# uc4h_esc_mini_v100.net
KiCad netlist of a schematic drawn in EAGLE
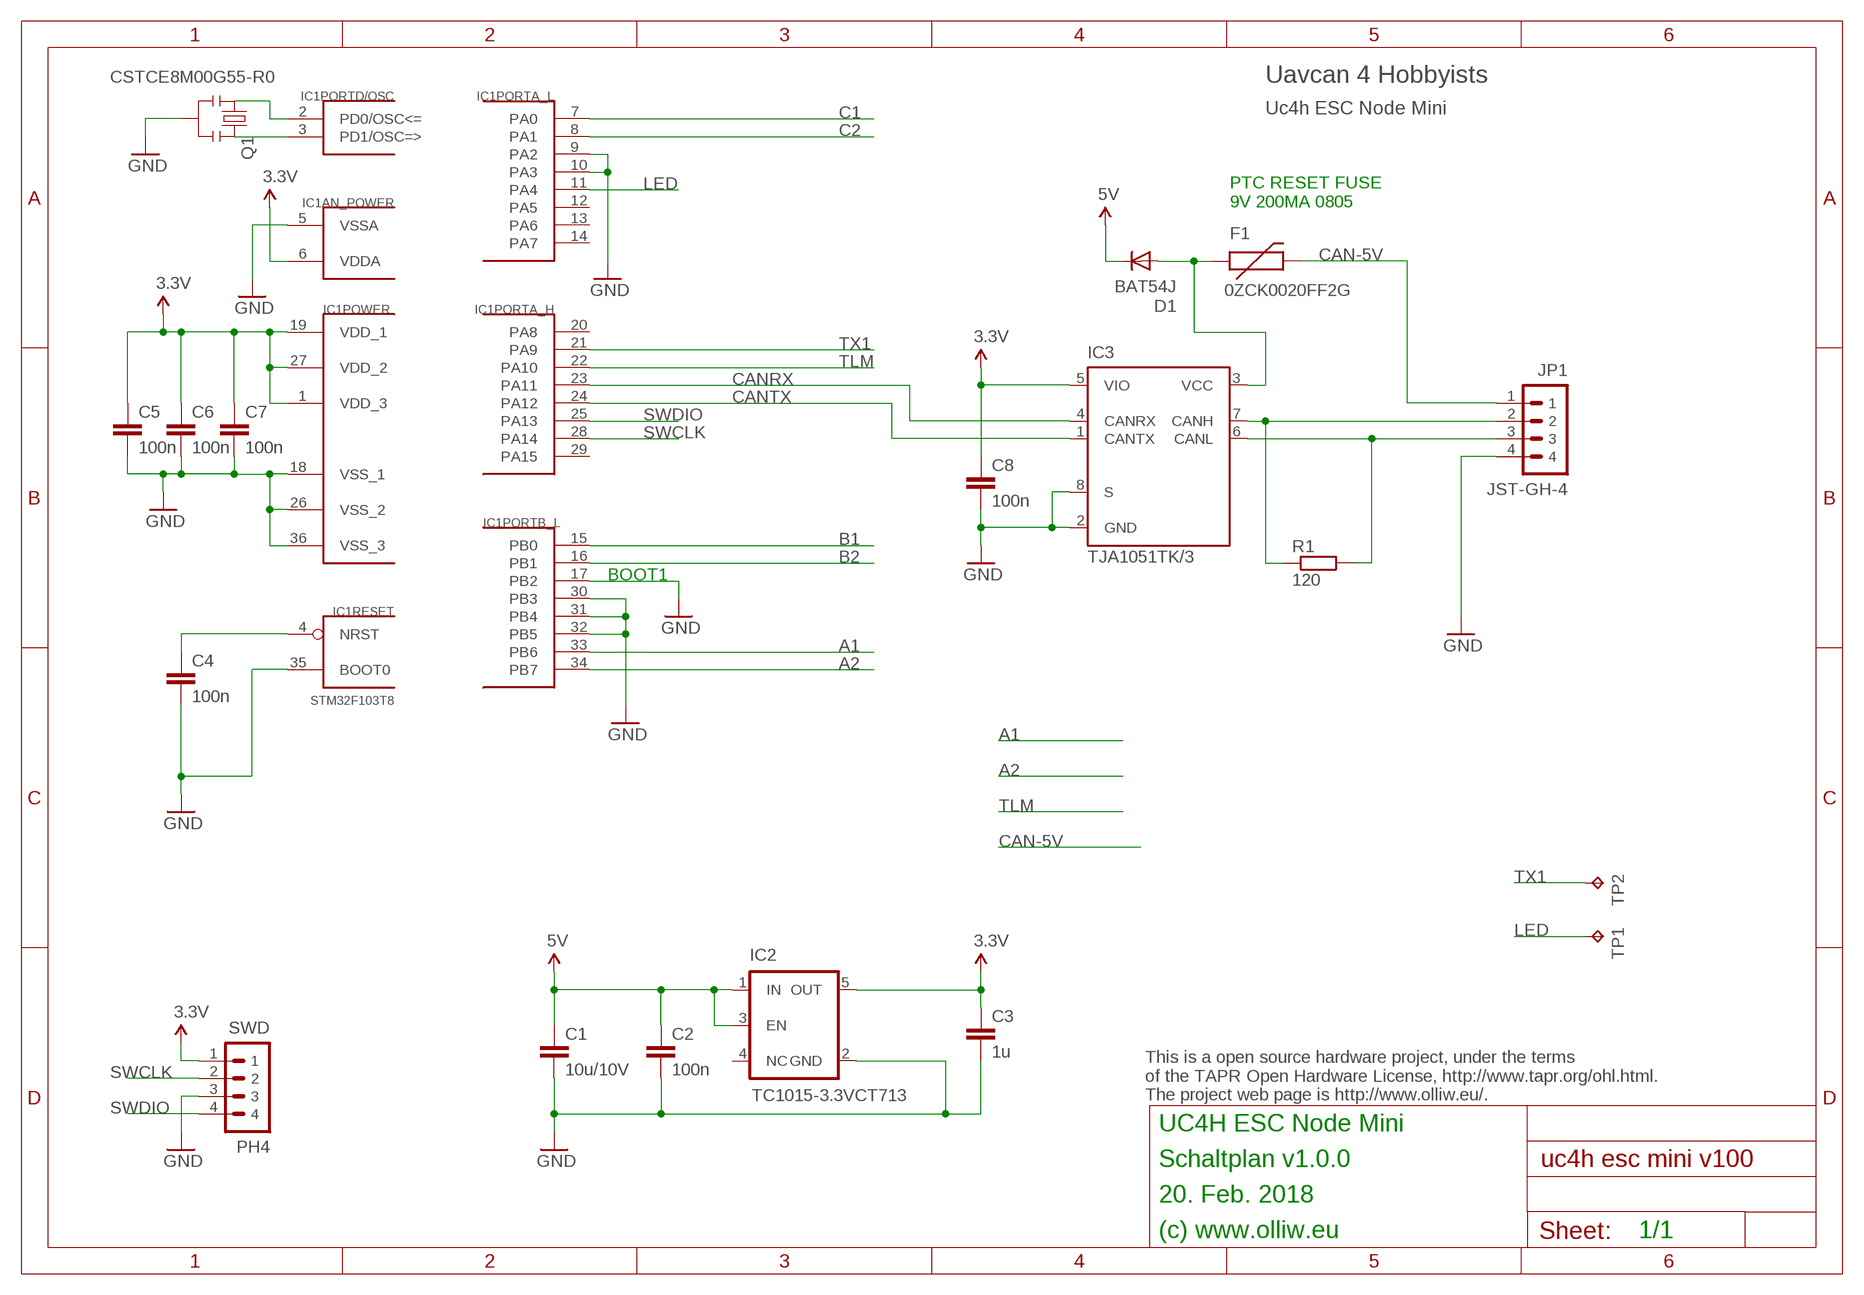
[diagram p0: schematic, sheet 1]

(export (version "E")
  (design (tool "Eeschema 10.0.6"))
  (components
    (comp (ref "C1")
      (value "10u/10V")
      (footprint "eagle-import:C1206")
      (libsource (lib "eagle-import") (part "C-EUC1206"))
    )
    (comp (ref "C2")
      (value "100n")
      (footprint "eagle-import:C0603K")
      (libsource (lib "eagle-import") (part "C-EUC0603K"))
    )
    (comp (ref "C3")
      (value "1u")
      (footprint "eagle-import:C0603K")
      (libsource (lib "eagle-import") (part "C-EUC0603K"))
    )
    (comp (ref "C4")
      (value "100n")
      (footprint "eagle-import:C0603K")
      (libsource (lib "eagle-import") (part "C-EUC0603K"))
    )
    (comp (ref "C5")
      (value "100n")
      (footprint "eagle-import:C0603K")
      (libsource (lib "eagle-import") (part "C-EUC0603K"))
    )
    (comp (ref "C6")
      (value "100n")
      (footprint "eagle-import:C0603K")
      (libsource (lib "eagle-import") (part "C-EUC0603K"))
    )
    (comp (ref "C7")
      (value "100n")
      (footprint "eagle-import:C0603K")
      (libsource (lib "eagle-import") (part "C-EUC0603K"))
    )
    (comp (ref "C8")
      (value "100n")
      (footprint "eagle-import:C0603K")
      (libsource (lib "eagle-import") (part "C-EUC0603K"))
    )
    (comp (ref "D1")
      (value "BAT54J")
      (footprint "eagle-import:SOD110-R")
      (libsource (lib "eagle-import") (part "DIODE-SOD110-R"))
    )
    (comp (ref "F1")
      (value "0ZCK0020FF2G")
      (footprint "eagle-import:FUSE-0805")
      (libsource (lib "eagle-import") (part "FUSE-PTCFUSE-0805"))
    )
    (comp (ref "IC1")
      (value "STM32F103T8")
      (footprint "eagle-import:VFQFPN36")
      (libsource (lib "eagle-import") (part "STM32F10XTXU6"))
    )
    (comp (ref "IC2")
      (value "TC1015-3.3VCT713")
      (footprint "eagle-import:SOT23-5")
      (libsource (lib "eagle-import") (part "V_REG_TPS76433SOT23-5"))
    )
    (comp (ref "IC3")
      (value "TJA1051TK/3")
      (footprint "eagle-import:HVSON8")
      (libsource (lib "eagle-import") (part "TJA1051TK/3"))
    )
    (comp (ref "JP1")
      (value "JST-GH-4")
      (footprint "eagle-import:SM04B-GHS-TB")
      (libsource (lib "eagle-import") (part "JST-GH-4"))
    )
    (comp (ref "Q1")
      (value "CSTCE8M00G55-R0")
      (footprint "eagle-import:RESONATOR-SMD")
      (libsource (lib "eagle-import") (part "RESONATORSMD"))
    )
    (comp (ref "R1")
      (value "120")
      (footprint "eagle-import:R0603")
      (libsource (lib "eagle-import") (part "R-EU_R0603"))
    )
    (comp (ref "SWD")
      (value "PH4")
      (footprint "eagle-import:4X1_1P27_OCT_BILEX")
      (libsource (lib "eagle-import") (part "P4X1_1P27-OCT_BILEX"))
    )
    (comp (ref "TP1")
      (value "TPB1,27")
      (footprint "eagle-import:B1,27")
      (libsource (lib "eagle-import") (part "TPB1,27"))
    )
    (comp (ref "TP2")
      (value "TPB1,27")
      (footprint "eagle-import:B1,27")
      (libsource (lib "eagle-import") (part "TPB1,27"))
    )
  )
  (nets
    (net (code "1") (name "/A1") (class "Default")
      (node (ref "IC1") (pin "33") (pinfunction "PB6_33") (pintype "bidirectional"))
    )
    (net (code "2") (name "/A2") (class "Default")
      (node (ref "IC1") (pin "34") (pinfunction "PB7_34") (pintype "bidirectional"))
    )
    (net (code "3") (name "/B1") (class "Default")
      (node (ref "IC1") (pin "15") (pinfunction "PB0_15") (pintype "bidirectional"))
    )
    (net (code "4") (name "/B2") (class "Default")
      (node (ref "IC1") (pin "16") (pinfunction "PB1_16") (pintype "bidirectional"))
    )
    (net (code "5") (name "/C1") (class "Default")
      (node (ref "IC1") (pin "7") (pinfunction "PA0_7") (pintype "bidirectional"))
    )
    (net (code "6") (name "/C2") (class "Default")
      (node (ref "IC1") (pin "8") (pinfunction "PA1_8") (pintype "bidirectional"))
    )
    (net (code "7") (name "/CAN-5V") (class "Default")
      (node (ref "F1") (pin "2") (pinfunction "2_2") (pintype "bidirectional"))
      (node (ref "JP1") (pin "1") (pinfunction "1_1") (pintype "passive"))
    )
    (net (code "8") (name "/CANRX") (class "Default")
      (node (ref "IC1") (pin "23") (pinfunction "PA11_23") (pintype "bidirectional"))
      (node (ref "IC3") (pin "4") (pinfunction "CANRX_4") (pintype "output"))
    )
    (net (code "9") (name "/CANTX") (class "Default")
      (node (ref "IC1") (pin "24") (pinfunction "PA12_24") (pintype "bidirectional"))
      (node (ref "IC3") (pin "1") (pinfunction "CANTX_1") (pintype "input"))
    )
    (net (code "10") (name "/LED") (class "Default")
      (node (ref "IC1") (pin "11") (pinfunction "PA4_11") (pintype "bidirectional"))
      (node (ref "TP1") (pin "TP") (pinfunction "TP_TP") (pintype "input"))
    )
    (net (code "11") (name "/SWCLK") (class "Default")
      (node (ref "IC1") (pin "28") (pinfunction "PA14_28") (pintype "bidirectional"))
      (node (ref "SWD") (pin "2") (pinfunction "2_2") (pintype "passive"))
    )
    (net (code "12") (name "/SWDIO") (class "Default")
      (node (ref "IC1") (pin "25") (pinfunction "PA13_25") (pintype "bidirectional"))
      (node (ref "SWD") (pin "4") (pinfunction "4_4") (pintype "passive"))
    )
    (net (code "13") (name "/TLM") (class "Default")
      (node (ref "IC1") (pin "22") (pinfunction "PA10_22") (pintype "bidirectional"))
    )
    (net (code "14") (name "/TX1") (class "Default")
      (node (ref "IC1") (pin "21") (pinfunction "PA9_21") (pintype "bidirectional"))
      (node (ref "TP2") (pin "TP") (pinfunction "TP_TP") (pintype "input"))
    )
    (net (code "15") (name "3.3V") (class "Default")
      (node (ref "C3") (pin "1") (pinfunction "1_1") (pintype "passive"))
      (node (ref "C5") (pin "1") (pinfunction "1_1") (pintype "passive"))
      (node (ref "C6") (pin "1") (pinfunction "1_1") (pintype "passive"))
      (node (ref "C7") (pin "1") (pinfunction "1_1") (pintype "passive"))
      (node (ref "C8") (pin "1") (pinfunction "1_1") (pintype "passive"))
      (node (ref "IC1") (pin "1") (pinfunction "VDD_3_1") (pintype "power_in"))
      (node (ref "IC1") (pin "19") (pinfunction "VDD_1_19") (pintype "power_in"))
      (node (ref "IC1") (pin "27") (pinfunction "VDD_2_27") (pintype "power_in"))
      (node (ref "IC1") (pin "6") (pinfunction "VDDA_6") (pintype "power_in"))
      (node (ref "IC2") (pin "5") (pinfunction "OUT_5") (pintype "output"))
      (node (ref "IC3") (pin "5") (pinfunction "VIO_5") (pintype "power_in"))
      (node (ref "SWD") (pin "1") (pinfunction "1_1") (pintype "passive"))
    )
    (net (code "16") (name "5V") (class "Default")
      (node (ref "C1") (pin "1") (pinfunction "1_1") (pintype "passive"))
      (node (ref "C2") (pin "1") (pinfunction "1_1") (pintype "passive"))
      (node (ref "D1") (pin "C") (pinfunction "C_C") (pintype "passive"))
      (node (ref "IC2") (pin "1") (pinfunction "IN_1") (pintype "power_in"))
      (node (ref "IC2") (pin "3") (pinfunction "EN_3") (pintype "input"))
    )
    (net (code "17") (name "GND") (class "Default")
      (node (ref "C1") (pin "2") (pinfunction "2_2") (pintype "passive"))
      (node (ref "C2") (pin "2") (pinfunction "2_2") (pintype "passive"))
      (node (ref "C3") (pin "2") (pinfunction "2_2") (pintype "passive"))
      (node (ref "C4") (pin "2") (pinfunction "2_2") (pintype "passive"))
      (node (ref "C5") (pin "2") (pinfunction "2_2") (pintype "passive"))
      (node (ref "C6") (pin "2") (pinfunction "2_2") (pintype "passive"))
      (node (ref "C7") (pin "2") (pinfunction "2_2") (pintype "passive"))
      (node (ref "C8") (pin "2") (pinfunction "2_2") (pintype "passive"))
      (node (ref "IC1") (pin "10") (pinfunction "PA3_10") (pintype "bidirectional"))
      (node (ref "IC1") (pin "17") (pinfunction "PB2_17") (pintype "bidirectional"))
      (node (ref "IC1") (pin "18") (pinfunction "VSS_1_18") (pintype "power_in"))
      (node (ref "IC1") (pin "26") (pinfunction "VSS_2_26") (pintype "power_in"))
      (node (ref "IC1") (pin "30") (pinfunction "PB3_30") (pintype "bidirectional"))
      (node (ref "IC1") (pin "31") (pinfunction "PB4_31") (pintype "bidirectional"))
      (node (ref "IC1") (pin "32") (pinfunction "PB5_32") (pintype "bidirectional"))
      (node (ref "IC1") (pin "35") (pinfunction "BOOT0_35") (pintype "input"))
      (node (ref "IC1") (pin "36") (pinfunction "VSS_3_36") (pintype "power_in"))
      (node (ref "IC1") (pin "5") (pinfunction "VSSA_5") (pintype "power_in"))
      (node (ref "IC1") (pin "9") (pinfunction "PA2_9") (pintype "bidirectional"))
      (node (ref "IC2") (pin "2") (pinfunction "GND_2") (pintype "power_in"))
      (node (ref "IC3") (pin "2") (pinfunction "GND_2") (pintype "power_in"))
      (node (ref "IC3") (pin "8") (pinfunction "S_8") (pintype "input"))
      (node (ref "JP1") (pin "4") (pinfunction "4_4") (pintype "passive"))
      (node (ref "Q1") (pin "2") (pinfunction "2_2") (pintype "passive"))
      (node (ref "SWD") (pin "3") (pinfunction "3_3") (pintype "passive"))
    )
    (net (code "18") (name "Net-(IC1E-PD0{slash}OSC<=)") (class "Default")
      (node (ref "IC1") (pin "2") (pinfunction "PD0/OSC<=_2") (pintype "bidirectional"))
      (node (ref "Q1") (pin "1") (pinfunction "1_1") (pintype "passive"))
    )
    (net (code "19") (name "Net-(IC1E-PD1{slash}OSC=>)") (class "Default")
      (node (ref "IC1") (pin "3") (pinfunction "PD1/OSC=>_3") (pintype "bidirectional"))
      (node (ref "Q1") (pin "3") (pinfunction "3_3") (pintype "passive"))
    )
    (net (code "20") (name "Net-(IC1G-NRST)") (class "Default")
      (node (ref "C4") (pin "1") (pinfunction "1_1") (pintype "passive"))
      (node (ref "IC1") (pin "4") (pinfunction "NRST_4") (pintype "input"))
    )
    (net (code "21") (name "Net-(IC3-CANH)") (class "Default")
      (node (ref "IC3") (pin "7") (pinfunction "CANH_7") (pintype "bidirectional"))
      (node (ref "JP1") (pin "2") (pinfunction "2_2") (pintype "passive"))
      (node (ref "R1") (pin "1") (pinfunction "1_1") (pintype "passive"))
    )
    (net (code "22") (name "Net-(IC3-CANL)") (class "Default")
      (node (ref "IC3") (pin "6") (pinfunction "CANL_6") (pintype "bidirectional"))
      (node (ref "JP1") (pin "3") (pinfunction "3_3") (pintype "passive"))
      (node (ref "R1") (pin "2") (pinfunction "2_2") (pintype "passive"))
    )
    (net (code "23") (name "Net-(IC3-VCC)") (class "Default")
      (node (ref "D1") (pin "A") (pinfunction "A_A") (pintype "passive"))
      (node (ref "F1") (pin "1") (pinfunction "1_1") (pintype "bidirectional"))
      (node (ref "IC3") (pin "3") (pinfunction "VCC_3") (pintype "power_in"))
    )
    (net (code "24") (name "unconnected-(IC1B-PA8-Pad20)") (class "Default")
      (node (ref "IC1") (pin "20") (pinfunction "PA8_20") (pintype "bidirectional"))
    )
    (net (code "25") (name "unconnected-(IC1B-PA15-Pad29)") (class "Default")
      (node (ref "IC1") (pin "29") (pinfunction "PA15_29") (pintype "bidirectional"))
    )
    (net (code "26") (name "unconnected-(IC1C-PA5-Pad12)") (class "Default")
      (node (ref "IC1") (pin "12") (pinfunction "PA5_12") (pintype "bidirectional"))
    )
    (net (code "27") (name "unconnected-(IC1C-PA6-Pad13)") (class "Default")
      (node (ref "IC1") (pin "13") (pinfunction "PA6_13") (pintype "bidirectional"))
    )
    (net (code "28") (name "unconnected-(IC1C-PA7-Pad14)") (class "Default")
      (node (ref "IC1") (pin "14") (pinfunction "PA7_14") (pintype "bidirectional"))
    )
    (net (code "29") (name "unconnected-(IC2-NC-Pad4)") (class "Default")
      (node (ref "IC2") (pin "4") (pinfunction "NC_4") (pintype "passive"))
    )
  )
)
